# power_supplies.net
KiCad netlist of a schematic drawn in Altium Designer
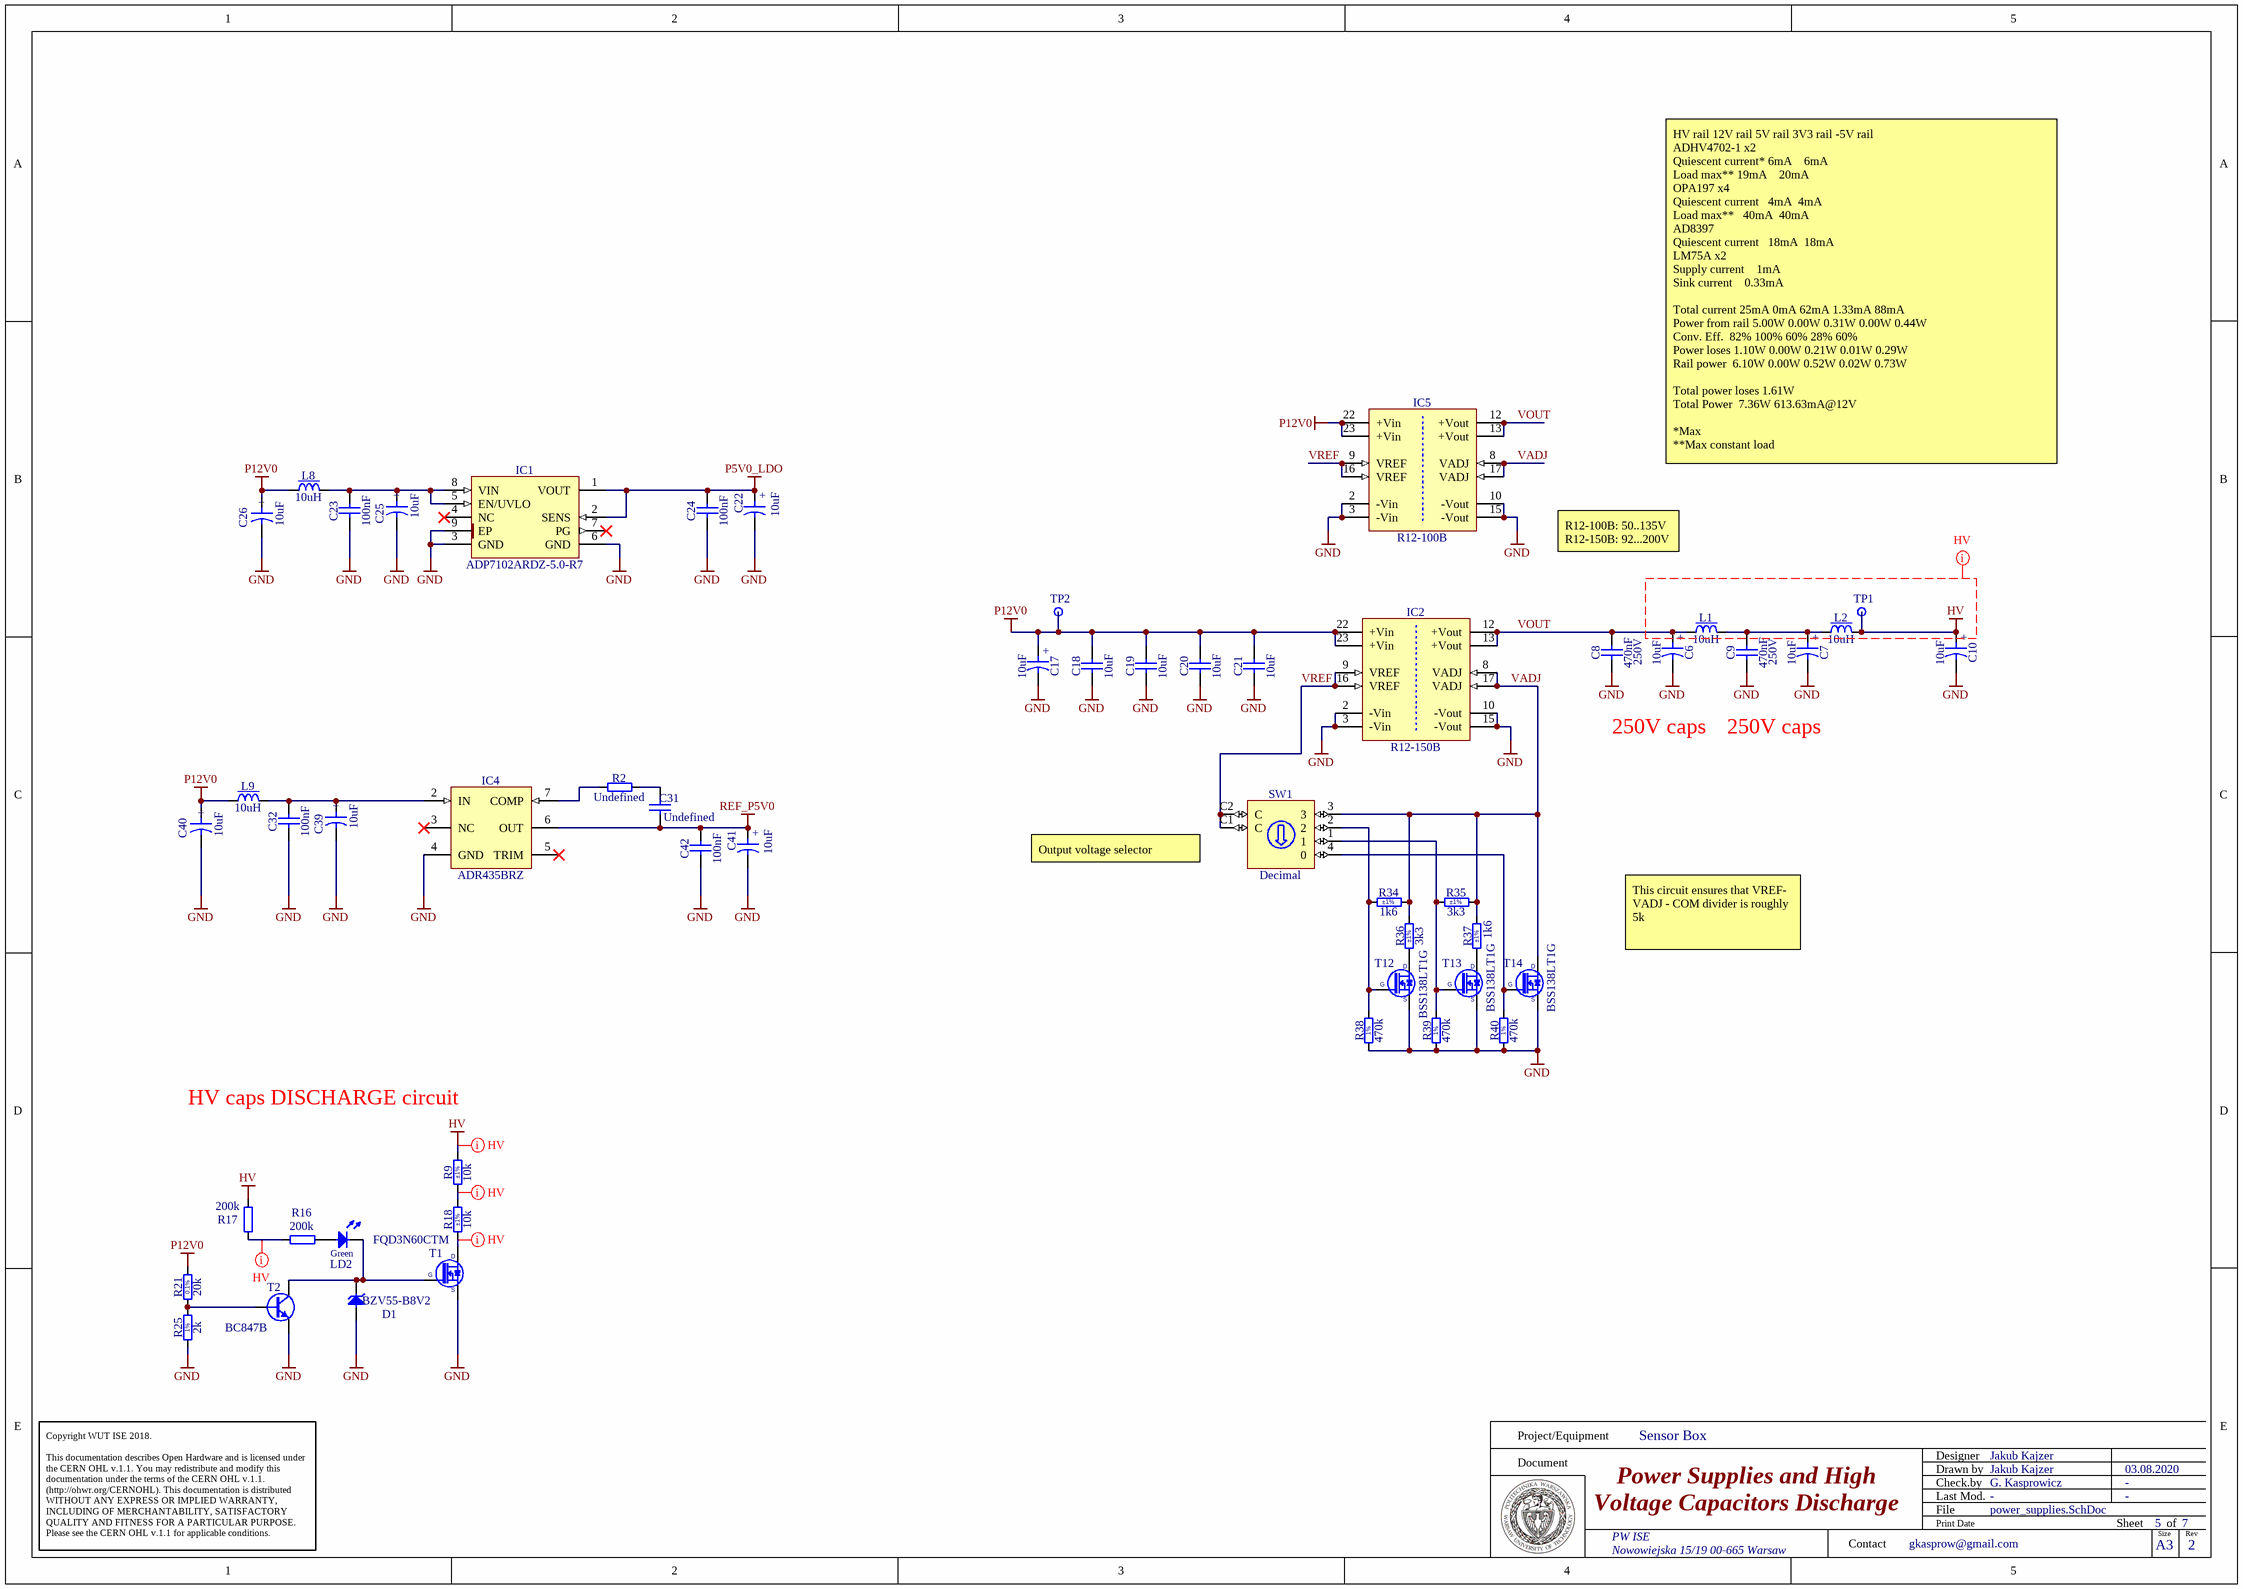
[diagram p0: power_supplies.SchDoc]

(export (version "E")
  (design (tool "Eeschema 10.0.6"))
  (components
    (comp (ref "C6")
      (value "10uF")
      (footprint "PcbLib:CAPAE")
      (description "Polarised capacitor")
      (fields (field (name "PART NUMBER") "CAE12.5-13.5_10UF_250V_20%") (field (name "VOLTAGE") "250V"))
      (libsource (lib "") (part "Capacitor - polarized_1"))
    )
    (comp (ref "C7")
      (value "10uF")
      (footprint "PcbLib:CAPAE")
      (description "Polarised capacitor")
      (fields (field (name "PART NUMBER") "CAE12.5-13.5_10UF_250V_20%") (field (name "VOLTAGE") "250V"))
      (libsource (lib "") (part "Capacitor - polarized_1"))
    )
    (comp (ref "C8")
      (value "470nF")
      (footprint "CAPC4532X185N")
      (description "Non-polarised capacitor")
      (fields
        (field (name "PART NUMBER") "CC1812_470NF_250V_10%_X7R_FT-CAP")
        (field (name "VOLTAGE") "250V")
        (field (name "TOLERANCE") "±10%")
        (field (name "AUTHOR") "CERN DEM JLC")
      )
      (libsource (lib "Capacitors") (part "Capacitor - non polarized"))
    )
    (comp (ref "C9")
      (value "470nF")
      (footprint "CAPC4532X185N")
      (description "Non-polarised capacitor")
      (fields
        (field (name "PART NUMBER") "CC1812_470NF_250V_10%_X7R_FT-CAP")
        (field (name "VOLTAGE") "250V")
        (field (name "TOLERANCE") "±10%")
        (field (name "AUTHOR") "CERN DEM JLC")
      )
      (libsource (lib "Capacitors") (part "Capacitor - non polarized"))
    )
    (comp (ref "C10")
      (value "10uF")
      (footprint "PcbLib:CAPAE")
      (description "Polarised capacitor")
      (fields (field (name "PART NUMBER") "CAE12.5-13.5_10UF_250V_20%") (field (name "VOLTAGE") "250V"))
      (libsource (lib "") (part "Capacitor - polarized_1"))
    )
    (comp (ref "C17")
      (value "10uF")
      (footprint "CAPMP6032X280N")
      (description "Polarised capacitor")
      (fields
        (field (name "PART NUMBER") "CTE6032-28_10UF_25V_10%_LESR0500")
        (field (name "VOLTAGE") "25V")
        (field (name "AUTHOR") "CERN DEM JLC")
      )
      (libsource (lib "") (part "Capacitor - polarized_1"))
    )
    (comp (ref "C18")
      (value "10uF")
      (footprint "CAPC2012X95N")
      (description "Non-polarised capacitor")
      (fields
        (field (name "PART NUMBER") "CC0805_10UF_25V_10%_X5R")
        (field (name "VOLTAGE") "25V")
        (field (name "AUTHOR") "CERN DEM JLC")
      )
      (libsource (lib "Capacitors") (part "Capacitor - non polarized"))
    )
    (comp (ref "C19")
      (value "10uF")
      (footprint "CAPC2012X95N")
      (description "Non-polarised capacitor")
      (fields
        (field (name "PART NUMBER") "CC0805_10UF_25V_10%_X5R")
        (field (name "VOLTAGE") "25V")
        (field (name "AUTHOR") "CERN DEM JLC")
      )
      (libsource (lib "Capacitors") (part "Capacitor - non polarized"))
    )
    (comp (ref "C20")
      (value "10uF")
      (footprint "CAPC2012X95N")
      (description "Non-polarised capacitor")
      (fields
        (field (name "PART NUMBER") "CC0805_10UF_25V_10%_X5R")
        (field (name "VOLTAGE") "25V")
        (field (name "AUTHOR") "CERN DEM JLC")
      )
      (libsource (lib "Capacitors") (part "Capacitor - non polarized"))
    )
    (comp (ref "C21")
      (value "10uF")
      (footprint "CAPC2012X95N")
      (description "Non-polarised capacitor")
      (fields
        (field (name "PART NUMBER") "CC0805_10UF_25V_10%_X5R")
        (field (name "VOLTAGE") "25V")
        (field (name "AUTHOR") "CERN DEM JLC")
      )
      (libsource (lib "Capacitors") (part "Capacitor - non polarized"))
    )
    (comp (ref "C22")
      (value "10uF")
      (footprint "CAPMP3216X180N")
      (description "Polarised capacitor")
      (fields
        (field (name "PART NUMBER") "CTE3216-18_10UF_16V_20%_AVX_TCJ")
        (field (name "VOLTAGE") "16V")
        (field (name "AUTHOR") "CERN DEM JLC")
      )
      (libsource (lib "") (part "Capacitor - polarized_1"))
    )
    (comp (ref "C23")
      (value "100nF")
      (footprint "CAPC1005X55N")
      (description "Non-polarised capacitor")
      (fields
        (field (name "PART NUMBER") "CC0402_100NF_16V_10%_X5R")
        (field (name "VOLTAGE") "16V")
        (field (name "AUTHOR") "CERN DEM JLC")
      )
      (libsource (lib "Capacitors") (part "Capacitor - non polarized"))
    )
    (comp (ref "C24")
      (value "100nF")
      (footprint "CAPC1005X55N")
      (description "Non-polarised capacitor")
      (fields
        (field (name "PART NUMBER") "CC0402_100NF_16V_10%_X5R")
        (field (name "VOLTAGE") "16V")
        (field (name "AUTHOR") "CERN DEM JLC")
      )
      (libsource (lib "Capacitors") (part "Capacitor - non polarized"))
    )
    (comp (ref "C25")
      (value "10uF")
      (footprint "CAPMP3216X180N")
      (description "Polarised capacitor")
      (fields
        (field (name "PART NUMBER") "CTE3216-18_10UF_16V_20%_AVX_TCJ")
        (field (name "VOLTAGE") "16V")
        (field (name "AUTHOR") "CERN DEM JLC")
      )
      (libsource (lib "Capacitors") (part "Capacitor - polarized"))
    )
    (comp (ref "C26")
      (value "10uF")
      (footprint "CAPMP6032X280N")
      (description "Polarised capacitor")
      (fields
        (field (name "PART NUMBER") "CTE6032-28_10UF_25V_10%_LESR0500")
        (field (name "VOLTAGE") "25V")
        (field (name "AUTHOR") "CERN DEM JLC")
      )
      (libsource (lib "Capacitors") (part "Capacitor - polarized"))
    )
    (comp (ref "C31")
      (value "Undefined")
      (footprint "CAPC1005X55N")
      (description "Non-polarised capacitor")
      (fields (field (name "PART NUMBER") "CC0402_NO-VALUE") (field (name "AUTHOR") "CERN DEM JLC"))
      (libsource (lib "Capacitors") (part "Capacitor - non polarized"))
    )
    (comp (ref "C32")
      (value "100nF")
      (footprint "CAPC1005X55N")
      (description "Non-polarised capacitor")
      (fields
        (field (name "PART NUMBER") "CC0402_100NF_16V_10%_X5R")
        (field (name "VOLTAGE") "16V")
        (field (name "AUTHOR") "CERN DEM JLC")
      )
      (libsource (lib "Capacitors") (part "Capacitor - non polarized"))
    )
    (comp (ref "C39")
      (value "10uF")
      (footprint "CAPMP3216X180N")
      (description "Polarised capacitor")
      (fields
        (field (name "PART NUMBER") "CTE3216-18_10UF_16V_20%_AVX_TCJ")
        (field (name "VOLTAGE") "16V")
        (field (name "AUTHOR") "CERN DEM JLC")
      )
      (libsource (lib "Capacitors") (part "Capacitor - polarized"))
    )
    (comp (ref "C40")
      (value "10uF")
      (footprint "CAPMP6032X280N")
      (description "Polarised capacitor")
      (fields
        (field (name "PART NUMBER") "CTE6032-28_10UF_25V_10%_LESR0500")
        (field (name "VOLTAGE") "25V")
        (field (name "AUTHOR") "CERN DEM JLC")
      )
      (libsource (lib "Capacitors") (part "Capacitor - polarized"))
    )
    (comp (ref "C41")
      (value "10uF")
      (footprint "CAPMP3216X180N")
      (description "Polarised capacitor")
      (fields
        (field (name "PART NUMBER") "CTE3216-18_10UF_16V_20%_AVX_TCJ")
        (field (name "VOLTAGE") "16V")
        (field (name "AUTHOR") "CERN DEM JLC")
      )
      (libsource (lib "") (part "Capacitor - polarized_1"))
    )
    (comp (ref "C42")
      (value "100nF")
      (footprint "CAPC1005X55N")
      (description "Non-polarised capacitor")
      (fields
        (field (name "PART NUMBER") "CC0402_100NF_16V_10%_X5R")
        (field (name "VOLTAGE") "16V")
        (field (name "AUTHOR") "CERN DEM JLC")
      )
      (libsource (lib "Capacitors") (part "Capacitor - non polarized"))
    )
    (comp (ref "D1")
      (value "BZV55-B8V2")
      (footprint "DIOMELF3515N")
      (description "Zener Diode")
      (fields
        (field (name "VOLTAGE") "8V2")
        (field (name "POWER") "500mW")
        (field (name "AUTHOR") "CERN DEM JLC")
      )
      (libsource (lib "ICs And Semiconductors") (part "Diode Zener"))
    )
    (comp (ref "IC1")
      (value "ADP7102ARDZ-5.0-R7")
      (footprint "SOIC127P600X175-9N-R241X309")
      (description "300 mA, Low Noise, CMOS LDO Linear Regulator")
      (fields (field (name "MANUFACTURER") "ANALOG DEVICES") (field (name "AUTHOR") "CERN DEM JLC"))
      (libsource (lib "ICs And Semiconductors") (part "ADP7102ARDZ-X.X-R7"))
    )
    (comp (ref "IC2")
      (value "R12-150B")
      (footprint "DCDC_RECOM_Rxx-B")
      (description "RECOM, Rxx-B Series, Single Output DCDC Converter")
      (fields (field (name "MANUFACTURER") "RECOM") (field (name "AUTHOR") "CERN DEM MR"))
      (libsource (lib "ICs And Semiconductors") (part "DCDC_RECOM_Rxx-B_Single Output"))
    )
    (comp (ref "IC4")
      (value "ADR435BRZ")
      (footprint "SOIC127P600X175-8N")
      (description "5V Ultralow Noise XFET Voltage References with Current Sink and Source Capability")
      (fields (field (name "MANUFACTURER") "ANALOG DEVICES") (field (name "AUTHOR") "CERN DEM JLC"))
      (libsource (lib "ICs And Semiconductors") (part "ADR435"))
    )
    (comp (ref "IC5")
      (value "R12-100B")
      (footprint "DCDC_RECOM_Rxx-B")
      (description "RECOM, Rxx-B Series, Single Output DCDC Converter")
      (fields (field (name "MANUFACTURER") "RECOM") (field (name "AUTHOR") "CERN DEM MR"))
      (libsource (lib "ICs And Semiconductors") (part "DCDC_RECOM_Rxx-B_Single Output"))
    )
    (comp (ref "L1")
      (value "10uH")
      (footprint "IND_MURATA-PS_8400")
      (description "Inductor With Core")
      (fields
        (field (name "PART NUMBER") "IND_10UH_10%_MURATA-PS_8400")
        (field (name "POWER") "950mA")
        (field (name "AUTHOR") "CERN DEM JLC")
      )
      (libsource (lib "Inductors & Transformers") (part "Inductor With Magnetic core"))
    )
    (comp (ref "L2")
      (value "10uH")
      (footprint "IND_MURATA-PS_8400")
      (description "Inductor With Core")
      (fields
        (field (name "PART NUMBER") "IND_10UH_10%_MURATA-PS_8400")
        (field (name "POWER") "950mA")
        (field (name "AUTHOR") "CERN DEM JLC")
      )
      (libsource (lib "Inductors & Transformers") (part "Inductor With Magnetic core"))
    )
    (comp (ref "L8")
      (value "10uH")
      (footprint "IND_MURATA-PS_8400")
      (description "Inductor With Core")
      (fields
        (field (name "PART NUMBER") "IND_10UH_10%_MURATA-PS_8400")
        (field (name "POWER") "950mA")
        (field (name "AUTHOR") "CERN DEM JLC")
      )
      (libsource (lib "Inductors & Transformers") (part "Inductor With Magnetic core"))
    )
    (comp (ref "L9")
      (value "10uH")
      (footprint "IND_MURATA-PS_8400")
      (description "Inductor With Core")
      (fields
        (field (name "PART NUMBER") "IND_10UH_10%_MURATA-PS_8400")
        (field (name "POWER") "950mA")
        (field (name "AUTHOR") "CERN DEM JLC")
      )
      (libsource (lib "Inductors & Transformers") (part "Inductor With Magnetic core"))
    )
    (comp (ref "LD2")
      (value "Green")
      (footprint "LED_AVAGO_HSMG-C150")
      (description "LED Green 1C 2A")
      (fields
        (field (name "PART NUMBER") "LED_AVAGO_HSMG-C150")
        (field (name "MANUFACTURER") "AVAGO TECHNOLOGIES")
        (field (name "AUTHOR") "CERN DEM MR")
      )
      (libsource (lib "ICs And Semiconductors") (part "LED Green 1C 2A"))
    )
    (comp (ref "R2")
      (value "Undefined")
      (footprint "RESC1005X40N")
      (description "Resistor")
      (fields (field (name "PART NUMBER") "R0402_NO-VALUE") (field (name "AUTHOR") "CERN DEM JLC"))
      (libsource (lib "Resistors") (part "Resistor"))
    )
    (comp (ref "R9")
      (value "10k")
      (footprint "RESC3216X65N")
      (description "Resistor - 1%")
      (fields
        (field (name "TOLERANCE") "±1%")
        (field (name "PART NUMBER") "R1206_10K_1%_0.25W_100PPM")
        (field (name "POWER") "0.25W")
        (field (name "AUTHOR") "CERN DEM JLC")
      )
      (libsource (lib "") (part "Resistor - 1%_1"))
    )
    (comp (ref "R16")
      (value "200k")
      (footprint "RESC3216X65N")
      (description "Resistor - 1%")
      (fields
        (field (name "PART NUMBER") "R1206_200K_1%_0.25W_100PPM")
        (field (name "POWER") "0.25W")
        (field (name "AUTHOR") "CERN DEM JLC")
      )
      (libsource (lib "") (part "Resistor - 1%_1"))
    )
    (comp (ref "R17")
      (value "200k")
      (footprint "RESC3216X65N")
      (description "Resistor - 1%")
      (fields
        (field (name "PART NUMBER") "R1206_200K_1%_0.25W_100PPM")
        (field (name "POWER") "0.25W")
        (field (name "AUTHOR") "CERN DEM JLC")
      )
      (libsource (lib "") (part "Resistor - 1%_1"))
    )
    (comp (ref "R18")
      (value "10k")
      (footprint "RESC3216X65N")
      (description "Resistor - 1%")
      (fields
        (field (name "TOLERANCE") "±1%")
        (field (name "PART NUMBER") "R1206_10K_1%_0.25W_100PPM")
        (field (name "POWER") "0.25W")
        (field (name "AUTHOR") "CERN DEM JLC")
      )
      (libsource (lib "") (part "Resistor - 1%_1"))
    )
    (comp (ref "R21")
      (value "20k")
      (footprint "RESC1608X55N")
      (description "Resistor - 0.1%")
      (fields
        (field (name "PART NUMBER") "R0603_20K_0.1%_0.063W_10PPM")
        (field (name "POWER") "0.063W")
        (field (name "AUTHOR") "CERN DEM JLC")
      )
      (libsource (lib "Resistors") (part "Resistor - 0.1%"))
    )
    (comp (ref "R25")
      (value "2k")
      (footprint "RESC1005X40N")
      (description "Resistor - 1%")
      (fields
        (field (name "PART NUMBER") "R0402_2K_1%_0.0625W_100PPM")
        (field (name "POWER") "0.0625W")
        (field (name "AUTHOR") "CERN DEM JLC")
      )
      (libsource (lib "Resistors") (part "Resistor - 1%"))
    )
    (comp (ref "R34")
      (value "1k6")
      (footprint "RESC1005X40N")
      (description "Resistor - 1%")
      (fields
        (field (name "TOLERANCE") "±1%")
        (field (name "PART NUMBER") "R0402_1K6_1%_0.0625W_100PPM")
        (field (name "POWER") "0.0625W")
        (field (name "AUTHOR") "CERN DEM JLC")
      )
      (libsource (lib "Resistors") (part "Resistor - 1%"))
    )
    (comp (ref "R35")
      (value "3k3")
      (footprint "RESC1005X40N")
      (description "Resistor - 1%")
      (fields
        (field (name "TOLERANCE") "±1%")
        (field (name "PART NUMBER") "R0402_3K3_1%_0.0625W_100PPM")
        (field (name "POWER") "0.0625W")
        (field (name "AUTHOR") "CERN DEM JLC")
      )
      (libsource (lib "Resistors") (part "Resistor - 1%"))
    )
    (comp (ref "R36")
      (value "3k3")
      (footprint "RESC1005X40N")
      (description "Resistor - 1%")
      (fields
        (field (name "TOLERANCE") "±1%")
        (field (name "PART NUMBER") "R0402_3K3_1%_0.0625W_100PPM")
        (field (name "POWER") "0.0625W")
        (field (name "AUTHOR") "CERN DEM JLC")
      )
      (libsource (lib "Resistors") (part "Resistor - 1%"))
    )
    (comp (ref "R37")
      (value "1k6")
      (footprint "RESC1005X40N")
      (description "Resistor - 1%")
      (fields
        (field (name "TOLERANCE") "±1%")
        (field (name "PART NUMBER") "R0402_1K6_1%_0.0625W_100PPM")
        (field (name "POWER") "0.0625W")
        (field (name "AUTHOR") "CERN DEM JLC")
      )
      (libsource (lib "Resistors") (part "Resistor - 1%"))
    )
    (comp (ref "R38")
      (value "470k")
      (footprint "RESC1005X40N")
      (description "Resistor - 1%")
      (fields
        (field (name "PART NUMBER") "R0402_470K_1%_0.0625W_100PPM")
        (field (name "POWER") "0.0625W")
        (field (name "AUTHOR") "CERN DEM JLC")
      )
      (libsource (lib "Resistors") (part "Resistor - 1%"))
    )
    (comp (ref "R39")
      (value "470k")
      (footprint "RESC1005X40N")
      (description "Resistor - 1%")
      (fields
        (field (name "PART NUMBER") "R0402_470K_1%_0.0625W_100PPM")
        (field (name "POWER") "0.0625W")
        (field (name "AUTHOR") "CERN DEM JLC")
      )
      (libsource (lib "Resistors") (part "Resistor - 1%"))
    )
    (comp (ref "R40")
      (value "470k")
      (footprint "RESC1005X40N")
      (description "Resistor - 1%")
      (fields
        (field (name "PART NUMBER") "R0402_470K_1%_0.0625W_100PPM")
        (field (name "POWER") "0.0625W")
        (field (name "AUTHOR") "CERN DEM JLC")
      )
      (libsource (lib "Resistors") (part "Resistor - 1%"))
    )
    (comp (ref "SW1")
      (value "Decimal")
      (footprint "SW_APEM_PT65121L508")
      (description "Rotary Code Switch 1 2 3 4 C1 C2")
      (fields
        (field (name "PART NUMBER") "SW_APEM_PT65121L508")
        (field (name "MANUFACTURER") "APEM")
        (field (name "AUTHOR") "CERN DEM MR")
      )
      (libsource (lib "Eletro-mechanical") (part "SW Rotary 1 2 3 4 C1 C2"))
    )
    (comp (ref "T1")
      (value "FQD3N60CTM")
      (footprint "TO228P991X239-3N-R552X520")
      (description "N-CHANNEL 600V, 2.4A, 3.4Ohm")
      (fields (field (name "MANUFACTURER") "ONSEMI") (field (name "AUTHOR") "GK"))
      (libsource (lib "Tranistors_Thyristors") (part "Q_FQD3N60CTM"))
    )
    (comp (ref "T2")
      (value "BC847B")
      (footprint "SOT95P230X110-3N")
      (description "NPN Transistor")
      (fields (field (name "MANUFACTURER") "NXP SEMICONDUCTORS") (field (name "AUTHOR") "CERN DEM JLC"))
      (libsource (lib "ICs And Semiconductors") (part "NPN B1 E2 C3"))
    )
    (comp (ref "T12")
      (value "BSS138LT1G")
      (footprint "SOT95P240X110-3N")
      (description "N-CHANNEL MOSFET WITH DIODE")
      (fields (field (name "MANUFACTURER") "ON SEMICONDUCTOR") (field (name "AUTHOR") "CERN DEM JLC"))
      (libsource (lib "ICs And Semiconductors") (part "N-MOSFET-D 1G 2S 3D"))
    )
    (comp (ref "T13")
      (value "BSS138LT1G")
      (footprint "SOT95P240X110-3N")
      (description "N-CHANNEL MOSFET WITH DIODE")
      (fields (field (name "MANUFACTURER") "ON SEMICONDUCTOR") (field (name "AUTHOR") "CERN DEM JLC"))
      (libsource (lib "ICs And Semiconductors") (part "N-MOSFET-D 1G 2S 3D"))
    )
    (comp (ref "T14")
      (value "BSS138LT1G")
      (footprint "SOT95P240X110-3N")
      (description "N-CHANNEL MOSFET WITH DIODE")
      (fields (field (name "MANUFACTURER") "ON SEMICONDUCTOR") (field (name "AUTHOR") "CERN DEM JLC"))
      (libsource (lib "ICs And Semiconductors") (part "N-MOSFET-D 1G 2S 3D"))
    )
    (comp (ref "TP1")
      (value "Test Point")
      (footprint "TPS127")
      (fields (field (name "PART NUMBER") "SMD_PAD_1.27X1.27MM") (field (name "AUTHOR") "CERN DEM JLC"))
      (libsource (lib "Eletro-mechanical") (part "Test Point"))
    )
    (comp (ref "TP2")
      (value "Test Point")
      (footprint "TPS127")
      (fields (field (name "PART NUMBER") "SMD_PAD_1.27X1.27MM") (field (name "AUTHOR") "CERN DEM JLC"))
      (libsource (lib "Eletro-mechanical") (part "Test Point"))
    )
  )
  (nets
    (net (code "3") (name "/VADJ") (class "Default")
      (node (ref "IC2") (pin "17") (pinfunction "VADJ_17") (pintype "input"))
      (node (ref "IC2") (pin "8") (pinfunction "VADJ_8") (pintype "input"))
      (node (ref "IC5") (pin "17") (pinfunction "VADJ_17") (pintype "input"))
      (node (ref "IC5") (pin "8") (pinfunction "VADJ_8") (pintype "input"))
      (node (ref "R34") (pin "2") (pinfunction "2_2") (pintype "passive"))
      (node (ref "R35") (pin "2") (pinfunction "2_2") (pintype "passive"))
      (node (ref "R36") (pin "2") (pinfunction "2_2") (pintype "passive"))
      (node (ref "R37") (pin "2") (pinfunction "2_2") (pintype "passive"))
      (node (ref "SW1") (pin "3") (pinfunction "3_3") (pintype "bidirectional"))
      (node (ref "T14") (pin "3") (pinfunction "D_3") (pintype "passive"))
    )
    (net (code "4") (name "/VOUT") (class "Default")
      (node (ref "C6") (pin "1") (pinfunction "1_1") (pintype "passive"))
      (node (ref "C8") (pin "2") (pinfunction "2_2") (pintype "passive"))
      (node (ref "IC2") (pin "12") (pinfunction "+Vout_12") (pintype "power_in"))
      (node (ref "IC2") (pin "13") (pinfunction "+Vout_13") (pintype "power_in"))
      (node (ref "IC5") (pin "12") (pinfunction "+Vout_12") (pintype "power_in"))
      (node (ref "IC5") (pin "13") (pinfunction "+Vout_13") (pintype "power_in"))
      (node (ref "L1") (pin "1") (pinfunction "1_1") (pintype "passive"))
    )
    (net (code "5") (name "/VREF") (class "Default")
      (node (ref "IC2") (pin "16") (pinfunction "VREF_16") (pintype "input"))
      (node (ref "IC2") (pin "9") (pinfunction "VREF_9") (pintype "input"))
      (node (ref "IC5") (pin "16") (pinfunction "VREF_16") (pintype "input"))
      (node (ref "IC5") (pin "9") (pinfunction "VREF_9") (pintype "input"))
      (node (ref "SW1") (pin "C1") (pinfunction "C_C1") (pintype "bidirectional"))
      (node (ref "SW1") (pin "C2") (pinfunction "C_C2") (pintype "bidirectional"))
    )
    (net (code "6") (name "GND") (class "Default")
      (node (ref "C10") (pin "2") (pinfunction "2_2") (pintype "passive"))
      (node (ref "C17") (pin "2") (pinfunction "2_2") (pintype "passive"))
      (node (ref "C18") (pin "1") (pinfunction "1_1") (pintype "passive"))
      (node (ref "C19") (pin "1") (pinfunction "1_1") (pintype "passive"))
      (node (ref "C20") (pin "1") (pinfunction "1_1") (pintype "passive"))
      (node (ref "C21") (pin "1") (pinfunction "1_1") (pintype "passive"))
      (node (ref "C22") (pin "2") (pinfunction "2_2") (pintype "passive"))
      (node (ref "C23") (pin "1") (pinfunction "1_1") (pintype "passive"))
      (node (ref "C24") (pin "1") (pinfunction "1_1") (pintype "passive"))
      (node (ref "C25") (pin "2") (pinfunction "2_2") (pintype "passive"))
      (node (ref "C26") (pin "2") (pinfunction "2_2") (pintype "passive"))
      (node (ref "C32") (pin "1") (pinfunction "1_1") (pintype "passive"))
      (node (ref "C39") (pin "2") (pinfunction "2_2") (pintype "passive"))
      (node (ref "C40") (pin "2") (pinfunction "2_2") (pintype "passive"))
      (node (ref "C41") (pin "2") (pinfunction "2_2") (pintype "passive"))
      (node (ref "C42") (pin "1") (pinfunction "1_1") (pintype "passive"))
      (node (ref "C6") (pin "2") (pinfunction "2_2") (pintype "passive"))
      (node (ref "C7") (pin "2") (pinfunction "2_2") (pintype "passive"))
      (node (ref "C8") (pin "1") (pinfunction "1_1") (pintype "passive"))
      (node (ref "C9") (pin "1") (pinfunction "1_1") (pintype "passive"))
      (node (ref "D1") (pin "2") (pinfunction "A_2") (pintype "passive"))
      (node (ref "IC1") (pin "3") (pinfunction "GND_3") (pintype "power_in"))
      (node (ref "IC1") (pin "6") (pinfunction "GND_6") (pintype "power_in"))
      (node (ref "IC1") (pin "9") (pinfunction "EP_9") (pintype "power_in"))
      (node (ref "IC2") (pin "10") (pinfunction "-Vout_10") (pintype "power_in"))
      (node (ref "IC2") (pin "15") (pinfunction "-Vout_15") (pintype "power_in"))
      (node (ref "IC2") (pin "2") (pinfunction "-Vin_2") (pintype "power_in"))
      (node (ref "IC2") (pin "3") (pinfunction "-Vin_3") (pintype "power_in"))
      (node (ref "IC4") (pin "4") (pinfunction "GND_4") (pintype "power_in"))
      (node (ref "IC5") (pin "10") (pinfunction "-Vout_10") (pintype "power_in"))
      (node (ref "IC5") (pin "15") (pinfunction "-Vout_15") (pintype "power_in"))
      (node (ref "IC5") (pin "2") (pinfunction "-Vin_2") (pintype "power_in"))
      (node (ref "IC5") (pin "3") (pinfunction "-Vin_3") (pintype "power_in"))
      (node (ref "R25") (pin "1") (pinfunction "1_1") (pintype "passive"))
      (node (ref "R38") (pin "1") (pinfunction "1_1") (pintype "passive"))
      (node (ref "R39") (pin "1") (pinfunction "1_1") (pintype "passive"))
      (node (ref "R40") (pin "1") (pinfunction "1_1") (pintype "passive"))
      (node (ref "T1") (pin "2") (pinfunction "S_2") (pintype "passive"))
      (node (ref "T12") (pin "2") (pinfunction "S_2") (pintype "passive"))
      (node (ref "T13") (pin "2") (pinfunction "S_2") (pintype "passive"))
      (node (ref "T14") (pin "2") (pinfunction "S_2") (pintype "passive"))
      (node (ref "T2") (pin "2") (pinfunction "E_2") (pintype "passive"))
    )
    (net (code "7") (name "HV") (class "Default")
      (node (ref "C10") (pin "1") (pinfunction "1_1") (pintype "passive"))
      (node (ref "L2") (pin "2") (pinfunction "2_2") (pintype "passive"))
      (node (ref "R17") (pin "2") (pinfunction "2_2") (pintype "passive"))
      (node (ref "R9") (pin "2") (pinfunction "2_2") (pintype "passive"))
      (node (ref "TP1") (pin "1") (pinfunction "1_1") (pintype "bidirectional"))
    )
    (net (code "8") (name "Net-(C7-Pad1)") (class "Default")
      (node (ref "C7") (pin "1") (pinfunction "1_1") (pintype "passive"))
      (node (ref "C9") (pin "2") (pinfunction "2_2") (pintype "passive"))
      (node (ref "L1") (pin "2") (pinfunction "2_2") (pintype "passive"))
      (node (ref "L2") (pin "1") (pinfunction "1_1") (pintype "passive"))
    )
    (net (code "9") (name "Net-(C31-Pad2)") (class "Default")
      (node (ref "C31") (pin "2") (pinfunction "2_2") (pintype "passive"))
      (node (ref "R2") (pin "2") (pinfunction "2_2") (pintype "passive"))
    )
    (net (code "10") (name "Net-(D1-C)") (class "Default")
      (node (ref "D1") (pin "1") (pinfunction "C_1") (pintype "passive"))
      (node (ref "LD2") (pin "1") (pinfunction "C_1") (pintype "passive"))
      (node (ref "T1") (pin "1") (pinfunction "G_1") (pintype "passive"))
      (node (ref "T2") (pin "3") (pinfunction "C_3") (pintype "passive"))
    )
    (net (code "11") (name "Net-(IC1-EN{slash}UVLO)") (class "Default")
      (node (ref "C23") (pin "2") (pinfunction "2_2") (pintype "passive"))
      (node (ref "C25") (pin "1") (pinfunction "1_1") (pintype "passive"))
      (node (ref "IC1") (pin "5") (pinfunction "EN/UVLO_5") (pintype "input"))
      (node (ref "IC1") (pin "8") (pinfunction "VIN_8") (pintype "input"))
      (node (ref "L8") (pin "2") (pinfunction "2_2") (pintype "passive"))
    )
    (net (code "12") (name "Net-(IC4-COMP)") (class "Default")
      (node (ref "IC4") (pin "7") (pinfunction "COMP_7") (pintype "input"))
      (node (ref "R2") (pin "1") (pinfunction "1_1") (pintype "passive"))
    )
    (net (code "13") (name "Net-(IC4-IN)") (class "Default")
      (node (ref "C32") (pin "2") (pinfunction "2_2") (pintype "passive"))
      (node (ref "C39") (pin "1") (pinfunction "1_1") (pintype "passive"))
      (node (ref "IC4") (pin "2") (pinfunction "IN_2") (pintype "input"))
      (node (ref "L9") (pin "2") (pinfunction "2_2") (pintype "passive"))
    )
    (net (code "14") (name "Net-(LD2-A)") (class "Default")
      (node (ref "LD2") (pin "2") (pinfunction "A_2") (pintype "passive"))
      (node (ref "R16") (pin "1") (pinfunction "1_1") (pintype "passive"))
    )
    (net (code "15") (name "Net-(R16-Pad2)") (class "Default")
      (node (ref "R16") (pin "2") (pinfunction "2_2") (pintype "passive"))
      (node (ref "R17") (pin "1") (pinfunction "1_1") (pintype "passive"))
    )
    (net (code "16") (name "Net-(R18-Pad2)") (class "Default")
      (node (ref "R18") (pin "2") (pinfunction "2_2") (pintype "passive"))
      (node (ref "R9") (pin "1") (pinfunction "1_1") (pintype "passive"))
    )
    (net (code "17") (name "Net-(SW1A-0)") (class "Default")
      (node (ref "R40") (pin "2") (pinfunction "2_2") (pintype "passive"))
      (node (ref "SW1") (pin "4") (pinfunction "0_4") (pintype "bidirectional"))
      (node (ref "T14") (pin "1") (pinfunction "G_1") (pintype "passive"))
    )
    (net (code "18") (name "Net-(T1-D)") (class "Default")
      (node (ref "R18") (pin "1") (pinfunction "1_1") (pintype "passive"))
      (node (ref "T1") (pin "3") (pinfunction "D_3") (pintype "passive"))
    )
    (net (code "19") (name "Net-(T2-B)") (class "Default")
      (node (ref "R21") (pin "1") (pinfunction "1_1") (pintype "passive"))
      (node (ref "R25") (pin "2") (pinfunction "2_2") (pintype "passive"))
      (node (ref "T2") (pin "1") (pinfunction "B_1") (pintype "passive"))
    )
    (net (code "20") (name "Net-(T12-D)") (class "Default")
      (node (ref "R36") (pin "1") (pinfunction "1_1") (pintype "passive"))
      (node (ref "T12") (pin "3") (pinfunction "D_3") (pintype "passive"))
    )
    (net (code "21") (name "Net-(T12-G)") (class "Default")
      (node (ref "R34") (pin "1") (pinfunction "1_1") (pintype "passive"))
      (node (ref "R38") (pin "2") (pinfunction "2_2") (pintype "passive"))
      (node (ref "SW1") (pin "2") (pinfunction "2_2") (pintype "bidirectional"))
      (node (ref "T12") (pin "1") (pinfunction "G_1") (pintype "passive"))
    )
    (net (code "22") (name "Net-(T13-D)") (class "Default")
      (node (ref "R37") (pin "1") (pinfunction "1_1") (pintype "passive"))
      (node (ref "T13") (pin "3") (pinfunction "D_3") (pintype "passive"))
    )
    (net (code "23") (name "Net-(T13-G)") (class "Default")
      (node (ref "R35") (pin "1") (pinfunction "1_1") (pintype "passive"))
      (node (ref "R39") (pin "2") (pinfunction "2_2") (pintype "passive"))
      (node (ref "SW1") (pin "1") (pinfunction "1_1") (pintype "bidirectional"))
      (node (ref "T13") (pin "1") (pinfunction "G_1") (pintype "passive"))
    )
    (net (code "24") (name "P5V0_LDO") (class "Default")
      (node (ref "C22") (pin "1") (pinfunction "1_1") (pintype "passive"))
      (node (ref "C24") (pin "2") (pinfunction "2_2") (pintype "passive"))
      (node (ref "IC1") (pin "1") (pinfunction "VOUT_1") (pintype "power_in"))
      (node (ref "IC1") (pin "2") (pinfunction "SENS_2") (pintype "input"))
    )
    (net (code "25") (name "P12V0") (class "Default")
      (node (ref "C17") (pin "1") (pinfunction "1_1") (pintype "passive"))
      (node (ref "C18") (pin "2") (pinfunction "2_2") (pintype "passive"))
      (node (ref "C19") (pin "2") (pinfunction "2_2") (pintype "passive"))
      (node (ref "C20") (pin "2") (pinfunction "2_2") (pintype "passive"))
      (node (ref "C21") (pin "2") (pinfunction "2_2") (pintype "passive"))
      (node (ref "C26") (pin "1") (pinfunction "1_1") (pintype "passive"))
      (node (ref "C40") (pin "1") (pinfunction "1_1") (pintype "passive"))
      (node (ref "IC2") (pin "22") (pinfunction "+Vin_22") (pintype "power_in"))
      (node (ref "IC2") (pin "23") (pinfunction "+Vin_23") (pintype "power_in"))
      (node (ref "IC5") (pin "22") (pinfunction "+Vin_22") (pintype "power_in"))
      (node (ref "IC5") (pin "23") (pinfunction "+Vin_23") (pintype "power_in"))
      (node (ref "L8") (pin "1") (pinfunction "1_1") (pintype "passive"))
      (node (ref "L9") (pin "1") (pinfunction "1_1") (pintype "passive"))
      (node (ref "R21") (pin "2") (pinfunction "2_2") (pintype "passive"))
      (node (ref "TP2") (pin "1") (pinfunction "1_1") (pintype "bidirectional"))
    )
    (net (code "26") (name "REF_P5V0") (class "Default")
      (node (ref "C31") (pin "1") (pinfunction "1_1") (pintype "passive"))
      (node (ref "C41") (pin "1") (pinfunction "1_1") (pintype "passive"))
      (node (ref "C42") (pin "2") (pinfunction "2_2") (pintype "passive"))
      (node (ref "IC4") (pin "6") (pinfunction "OUT_6") (pintype "power_in"))
    )
    (net (code "27") (name "unconnected-(IC1-NC-Pad4)") (class "Default")
      (node (ref "IC1") (pin "4") (pinfunction "NC_4") (pintype "passive+no_connect"))
    )
    (net (code "28") (name "unconnected-(IC1-PG-Pad7)") (class "Default")
      (node (ref "IC1") (pin "7") (pinfunction "PG_7") (pintype "output+no_connect"))
    )
    (net (code "29") (name "unconnected-(IC4-NC-Pad3)") (class "Default")
      (node (ref "IC4") (pin "3") (pinfunction "NC_3") (pintype "passive+no_connect"))
    )
    (net (code "30") (name "unconnected-(IC4-TRIM-Pad5)") (class "Default")
      (node (ref "IC4") (pin "5") (pinfunction "TRIM_5") (pintype "passive+no_connect"))
    )
  )
)
